# 7Segment_Hex_Display.net
KiCad netlist of a schematic drawn in EAGLE
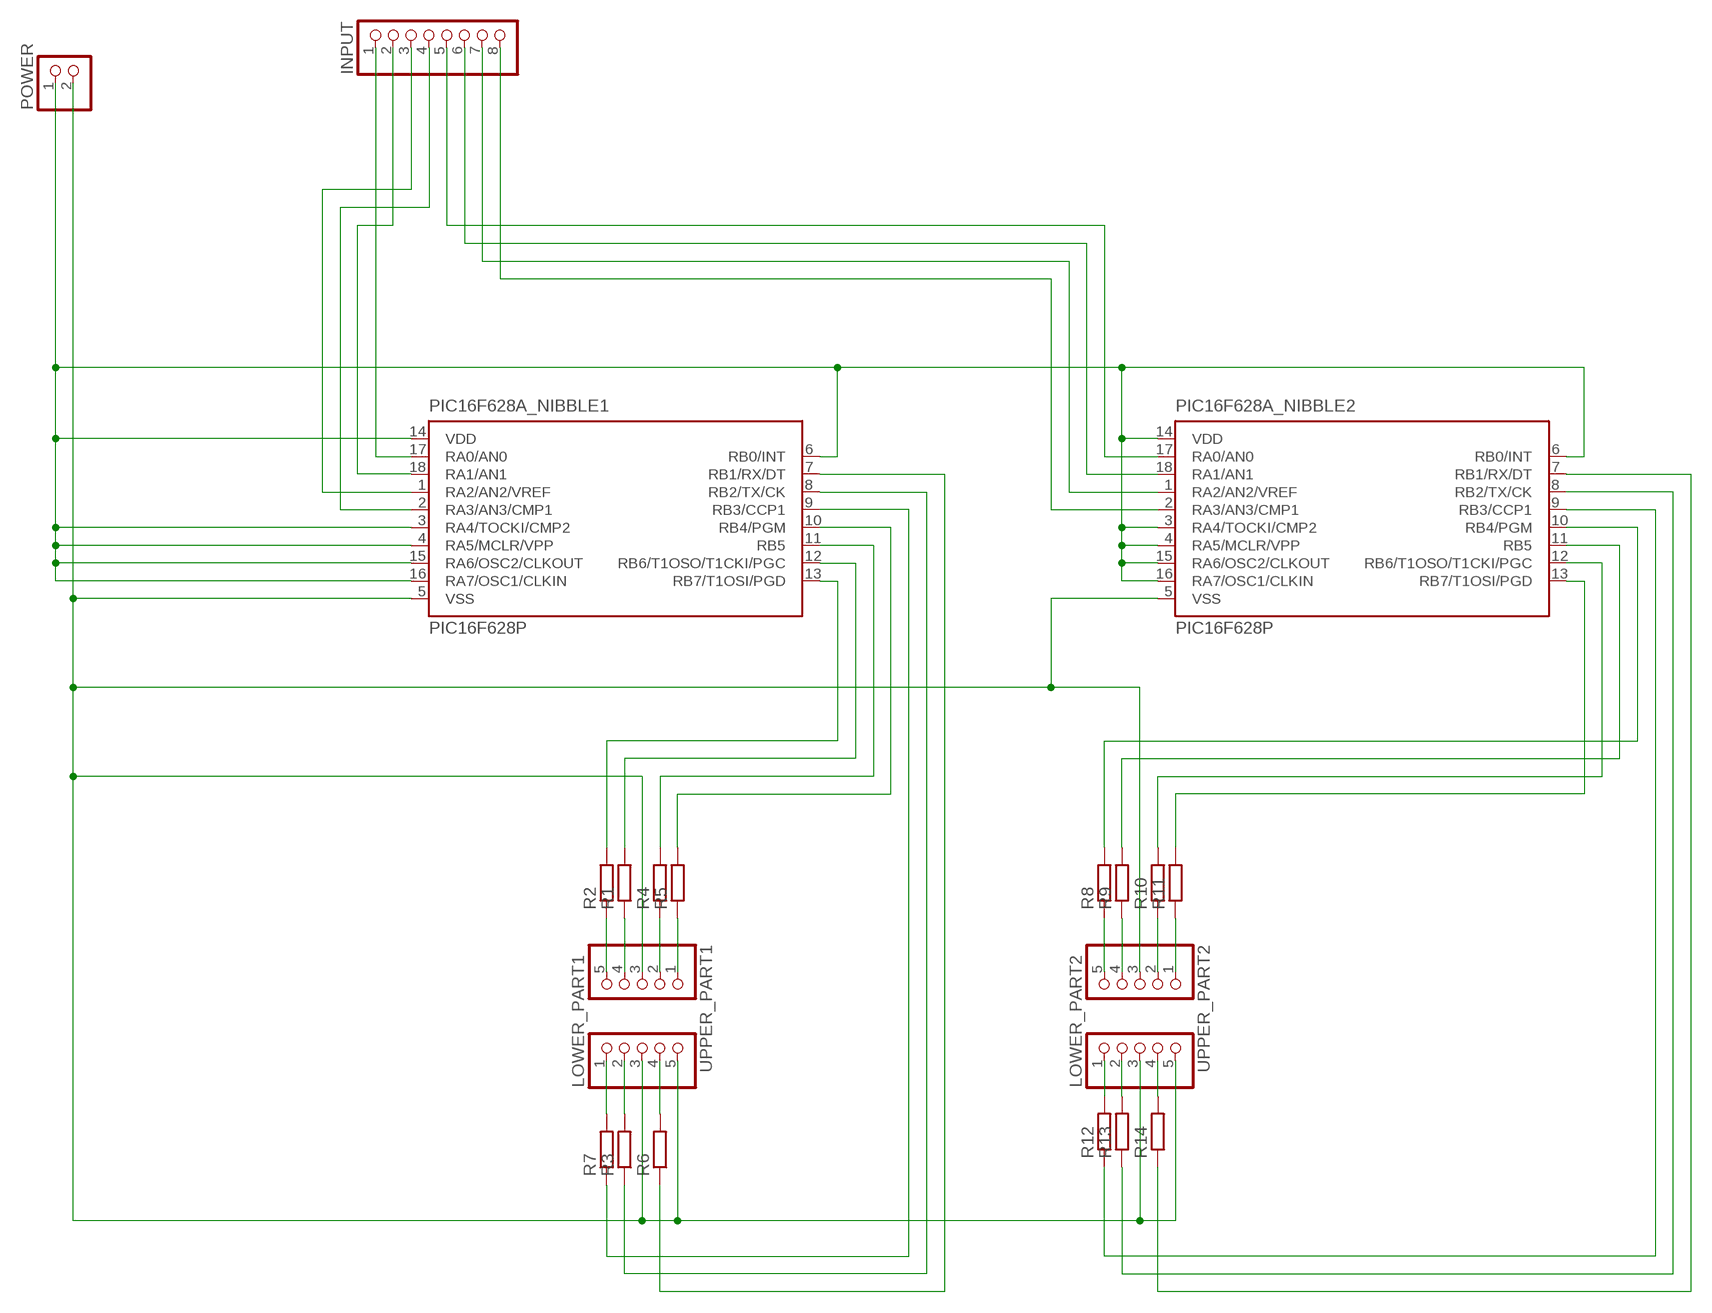
[diagram p0: schematic, sheet 1]

(export (version "E")
  (design (tool "Eeschema 10.0.6"))
  (components
    (comp (ref "INPUT")
      (value "PINHD-1X8")
      (footprint "eagle-import:1X08")
      (libsource (lib "eagle-import") (part "PINHD-1X8"))
    )
    (comp (ref "LOWER_PART1")
      (value "PINHD-1X5")
      (footprint "eagle-import:1X05")
      (libsource (lib "eagle-import") (part "PINHD-1X5"))
    )
    (comp (ref "LOWER_PART2")
      (value "PINHD-1X5")
      (footprint "eagle-import:1X05")
      (libsource (lib "eagle-import") (part "PINHD-1X5"))
    )
    (comp (ref "PIC16F628A_NIBBLE1")
      (value "PIC16F628P")
      (footprint "eagle-import:DIL18")
      (fields (field (name "MF") "MICROCHIP") (field (name "MPN") "PIC16F628-04I/P"))
      (libsource (lib "eagle-import") (part "PIC16F62P8"))
    )
    (comp (ref "PIC16F628A_NIBBLE2")
      (value "PIC16F628P")
      (footprint "eagle-import:DIL18")
      (fields (field (name "MF") "MICROCHIP") (field (name "MPN") "PIC16F628-04I/P"))
      (libsource (lib "eagle-import") (part "PIC16F62P8"))
    )
    (comp (ref "POWER")
      (value "PINHD-1X2")
      (footprint "eagle-import:1X02")
      (libsource (lib "eagle-import") (part "PINHD-1X2"))
    )
    (comp (ref "R1")
      (value "R-EU_0207/10")
      (footprint "eagle-import:0207_10")
      (libsource (lib "eagle-import") (part "R-EU_0207/10"))
    )
    (comp (ref "R2")
      (value "R-EU_0207/10")
      (footprint "eagle-import:0207_10")
      (libsource (lib "eagle-import") (part "R-EU_0207/10"))
    )
    (comp (ref "R3")
      (value "R-EU_0207/10")
      (footprint "eagle-import:0207_10")
      (libsource (lib "eagle-import") (part "R-EU_0207/10"))
    )
    (comp (ref "R4")
      (value "R-EU_0207/10")
      (footprint "eagle-import:0207_10")
      (libsource (lib "eagle-import") (part "R-EU_0207/10"))
    )
    (comp (ref "R5")
      (value "R-EU_0207/10")
      (footprint "eagle-import:0207_10")
      (libsource (lib "eagle-import") (part "R-EU_0207/10"))
    )
    (comp (ref "R6")
      (value "R-EU_0207/10")
      (footprint "eagle-import:0207_10")
      (libsource (lib "eagle-import") (part "R-EU_0207/10"))
    )
    (comp (ref "R7")
      (value "R-EU_0207/10")
      (footprint "eagle-import:0207_10")
      (libsource (lib "eagle-import") (part "R-EU_0207/10"))
    )
    (comp (ref "R8")
      (value "R-EU_0207/10")
      (footprint "eagle-import:0207_10")
      (libsource (lib "eagle-import") (part "R-EU_0207/10"))
    )
    (comp (ref "R9")
      (value "R-EU_0207/10")
      (footprint "eagle-import:0207_10")
      (libsource (lib "eagle-import") (part "R-EU_0207/10"))
    )
    (comp (ref "R10")
      (value "R-EU_0207/10")
      (footprint "eagle-import:0207_10")
      (libsource (lib "eagle-import") (part "R-EU_0207/10"))
    )
    (comp (ref "R11")
      (value "R-EU_0207/10")
      (footprint "eagle-import:0207_10")
      (libsource (lib "eagle-import") (part "R-EU_0207/10"))
    )
    (comp (ref "R12")
      (value "R-EU_0207/10")
      (footprint "eagle-import:0207_10")
      (libsource (lib "eagle-import") (part "R-EU_0207/10"))
    )
    (comp (ref "R13")
      (value "R-EU_0207/10")
      (footprint "eagle-import:0207_10")
      (libsource (lib "eagle-import") (part "R-EU_0207/10"))
    )
    (comp (ref "R14")
      (value "R-EU_0207/10")
      (footprint "eagle-import:0207_10")
      (libsource (lib "eagle-import") (part "R-EU_0207/10"))
    )
    (comp (ref "UPPER_PART1")
      (value "PINHD-1X5")
      (footprint "eagle-import:1X05")
      (libsource (lib "eagle-import") (part "PINHD-1X5"))
    )
    (comp (ref "UPPER_PART2")
      (value "PINHD-1X5")
      (footprint "eagle-import:1X05")
      (libsource (lib "eagle-import") (part "PINHD-1X5"))
    )
  )
  (nets
    (net (code "1") (name "Net-(LOWER_PART1-Pad1)") (class "Default")
      (node (ref "LOWER_PART1") (pin "1") (pinfunction "1_1") (pintype "passive"))
      (node (ref "R7") (pin "2") (pinfunction "2_2") (pintype "passive"))
    )
    (net (code "2") (name "Net-(LOWER_PART1-Pad2)") (class "Default")
      (node (ref "LOWER_PART1") (pin "2") (pinfunction "2_2") (pintype "passive"))
      (node (ref "R3") (pin "2") (pinfunction "2_2") (pintype "passive"))
    )
    (net (code "3") (name "Net-(LOWER_PART1-Pad4)") (class "Default")
      (node (ref "LOWER_PART1") (pin "4") (pinfunction "4_4") (pintype "passive"))
      (node (ref "R6") (pin "2") (pinfunction "2_2") (pintype "passive"))
    )
    (net (code "4") (name "Net-(LOWER_PART2-Pad1)") (class "Default")
      (node (ref "LOWER_PART2") (pin "1") (pinfunction "1_1") (pintype "passive"))
      (node (ref "R12") (pin "2") (pinfunction "2_2") (pintype "passive"))
    )
    (net (code "5") (name "Net-(LOWER_PART2-Pad2)") (class "Default")
      (node (ref "LOWER_PART2") (pin "2") (pinfunction "2_2") (pintype "passive"))
      (node (ref "R13") (pin "2") (pinfunction "2_2") (pintype "passive"))
    )
    (net (code "6") (name "Net-(LOWER_PART2-Pad4)") (class "Default")
      (node (ref "LOWER_PART2") (pin "4") (pinfunction "4_4") (pintype "passive"))
      (node (ref "R14") (pin "2") (pinfunction "2_2") (pintype "passive"))
    )
    (net (code "7") (name "Net-(PIC16F628A_NIBBLE1-RA0{slash}AN0)") (class "Default")
      (node (ref "INPUT") (pin "1") (pinfunction "1_1") (pintype "passive"))
      (node (ref "PIC16F628A_NIBBLE1") (pin "17") (pinfunction "RA0/AN0_17") (pintype "bidirectional"))
    )
    (net (code "8") (name "Net-(PIC16F628A_NIBBLE1-RA1{slash}AN1)") (class "Default")
      (node (ref "INPUT") (pin "2") (pinfunction "2_2") (pintype "passive"))
      (node (ref "PIC16F628A_NIBBLE1") (pin "18") (pinfunction "RA1/AN1_18") (pintype "bidirectional"))
    )
    (net (code "9") (name "Net-(PIC16F628A_NIBBLE1-RA2{slash}AN2{slash}VREF)") (class "Default")
      (node (ref "INPUT") (pin "3") (pinfunction "3_3") (pintype "passive"))
      (node (ref "PIC16F628A_NIBBLE1") (pin "1") (pinfunction "RA2/AN2/VREF_1") (pintype "bidirectional"))
    )
    (net (code "10") (name "Net-(PIC16F628A_NIBBLE1-RA3{slash}AN3{slash}CMP1)") (class "Default")
      (node (ref "INPUT") (pin "4") (pinfunction "4_4") (pintype "passive"))
      (node (ref "PIC16F628A_NIBBLE1") (pin "2") (pinfunction "RA3/AN3/CMP1_2") (pintype "bidirectional"))
    )
    (net (code "11") (name "Net-(PIC16F628A_NIBBLE1-RA4{slash}TOCKI{slash}CMP2)") (class "Default")
      (node (ref "PIC16F628A_NIBBLE1") (pin "14") (pinfunction "VDD_14") (pintype "power_in"))
      (node (ref "PIC16F628A_NIBBLE1") (pin "15") (pinfunction "RA6/OSC2/CLKOUT_15") (pintype "bidirectional"))
      (node (ref "PIC16F628A_NIBBLE1") (pin "16") (pinfunction "RA7/OSC1/CLKIN_16") (pintype "bidirectional"))
      (node (ref "PIC16F628A_NIBBLE1") (pin "3") (pinfunction "RA4/TOCKI/CMP2_3") (pintype "bidirectional"))
      (node (ref "PIC16F628A_NIBBLE1") (pin "4") (pinfunction "RA5/MCLR/VPP_4") (pintype "bidirectional"))
      (node (ref "PIC16F628A_NIBBLE1") (pin "6") (pinfunction "RB0/INT_6") (pintype "bidirectional"))
      (node (ref "PIC16F628A_NIBBLE2") (pin "14") (pinfunction "VDD_14") (pintype "power_in"))
      (node (ref "PIC16F628A_NIBBLE2") (pin "15") (pinfunction "RA6/OSC2/CLKOUT_15") (pintype "bidirectional"))
      (node (ref "PIC16F628A_NIBBLE2") (pin "16") (pinfunction "RA7/OSC1/CLKIN_16") (pintype "bidirectional"))
      (node (ref "PIC16F628A_NIBBLE2") (pin "3") (pinfunction "RA4/TOCKI/CMP2_3") (pintype "bidirectional"))
      (node (ref "PIC16F628A_NIBBLE2") (pin "4") (pinfunction "RA5/MCLR/VPP_4") (pintype "bidirectional"))
      (node (ref "PIC16F628A_NIBBLE2") (pin "6") (pinfunction "RB0/INT_6") (pintype "bidirectional"))
      (node (ref "POWER") (pin "1") (pinfunction "1_1") (pintype "passive"))
    )
    (net (code "12") (name "Net-(PIC16F628A_NIBBLE1-RB1{slash}RX{slash}DT)") (class "Default")
      (node (ref "PIC16F628A_NIBBLE1") (pin "7") (pinfunction "RB1/RX/DT_7") (pintype "bidirectional"))
      (node (ref "R6") (pin "1") (pinfunction "1_1") (pintype "passive"))
    )
    (net (code "13") (name "Net-(PIC16F628A_NIBBLE1-RB2{slash}TX{slash}CK)") (class "Default")
      (node (ref "PIC16F628A_NIBBLE1") (pin "8") (pinfunction "RB2/TX/CK_8") (pintype "bidirectional"))
      (node (ref "R3") (pin "1") (pinfunction "1_1") (pintype "passive"))
    )
    (net (code "14") (name "Net-(PIC16F628A_NIBBLE1-RB3{slash}CCP1)") (class "Default")
      (node (ref "PIC16F628A_NIBBLE1") (pin "9") (pinfunction "RB3/CCP1_9") (pintype "bidirectional"))
      (node (ref "R7") (pin "1") (pinfunction "1_1") (pintype "passive"))
    )
    (net (code "15") (name "Net-(PIC16F628A_NIBBLE1-RB4{slash}PGM)") (class "Default")
      (node (ref "PIC16F628A_NIBBLE1") (pin "10") (pinfunction "RB4/PGM_10") (pintype "bidirectional"))
      (node (ref "R5") (pin "2") (pinfunction "2_2") (pintype "passive"))
    )
    (net (code "16") (name "Net-(PIC16F628A_NIBBLE1-RB5)") (class "Default")
      (node (ref "PIC16F628A_NIBBLE1") (pin "11") (pinfunction "RB5_11") (pintype "bidirectional"))
      (node (ref "R4") (pin "2") (pinfunction "2_2") (pintype "passive"))
    )
    (net (code "17") (name "Net-(PIC16F628A_NIBBLE1-RB6{slash}T1OSO{slash}T1CKI{slash}PGC)") (class "Default")
      (node (ref "PIC16F628A_NIBBLE1") (pin "12") (pinfunction "RB6/T1OSO/T1CKI/PGC_12") (pintype "bidirectional"))
      (node (ref "R1") (pin "2") (pinfunction "2_2") (pintype "passive"))
    )
    (net (code "18") (name "Net-(PIC16F628A_NIBBLE1-RB7{slash}T1OSI{slash}PGD)") (class "Default")
      (node (ref "PIC16F628A_NIBBLE1") (pin "13") (pinfunction "RB7/T1OSI/PGD_13") (pintype "bidirectional"))
      (node (ref "R2") (pin "2") (pinfunction "2_2") (pintype "passive"))
    )
    (net (code "19") (name "Net-(PIC16F628A_NIBBLE1-VSS)") (class "Default")
      (node (ref "LOWER_PART1") (pin "3") (pinfunction "3_3") (pintype "passive"))
      (node (ref "LOWER_PART1") (pin "5") (pinfunction "5_5") (pintype "passive"))
      (node (ref "LOWER_PART2") (pin "3") (pinfunction "3_3") (pintype "passive"))
      (node (ref "LOWER_PART2") (pin "5") (pinfunction "5_5") (pintype "passive"))
      (node (ref "PIC16F628A_NIBBLE1") (pin "5") (pinfunction "VSS_5") (pintype "power_in"))
      (node (ref "PIC16F628A_NIBBLE2") (pin "5") (pinfunction "VSS_5") (pintype "power_in"))
      (node (ref "POWER") (pin "2") (pinfunction "2_2") (pintype "passive"))
      (node (ref "UPPER_PART1") (pin "3") (pinfunction "3_3") (pintype "passive"))
      (node (ref "UPPER_PART2") (pin "3") (pinfunction "3_3") (pintype "passive"))
    )
    (net (code "20") (name "Net-(PIC16F628A_NIBBLE2-RA0{slash}AN0)") (class "Default")
      (node (ref "INPUT") (pin "5") (pinfunction "5_5") (pintype "passive"))
      (node (ref "PIC16F628A_NIBBLE2") (pin "17") (pinfunction "RA0/AN0_17") (pintype "bidirectional"))
    )
    (net (code "21") (name "Net-(PIC16F628A_NIBBLE2-RA1{slash}AN1)") (class "Default")
      (node (ref "INPUT") (pin "6") (pinfunction "6_6") (pintype "passive"))
      (node (ref "PIC16F628A_NIBBLE2") (pin "18") (pinfunction "RA1/AN1_18") (pintype "bidirectional"))
    )
    (net (code "22") (name "Net-(PIC16F628A_NIBBLE2-RA2{slash}AN2{slash}VREF)") (class "Default")
      (node (ref "INPUT") (pin "7") (pinfunction "7_7") (pintype "passive"))
      (node (ref "PIC16F628A_NIBBLE2") (pin "1") (pinfunction "RA2/AN2/VREF_1") (pintype "bidirectional"))
    )
    (net (code "23") (name "Net-(PIC16F628A_NIBBLE2-RA3{slash}AN3{slash}CMP1)") (class "Default")
      (node (ref "INPUT") (pin "8") (pinfunction "8_8") (pintype "passive"))
      (node (ref "PIC16F628A_NIBBLE2") (pin "2") (pinfunction "RA3/AN3/CMP1_2") (pintype "bidirectional"))
    )
    (net (code "24") (name "Net-(PIC16F628A_NIBBLE2-RB1{slash}RX{slash}DT)") (class "Default")
      (node (ref "PIC16F628A_NIBBLE2") (pin "7") (pinfunction "RB1/RX/DT_7") (pintype "bidirectional"))
      (node (ref "R14") (pin "1") (pinfunction "1_1") (pintype "passive"))
    )
    (net (code "25") (name "Net-(PIC16F628A_NIBBLE2-RB2{slash}TX{slash}CK)") (class "Default")
      (node (ref "PIC16F628A_NIBBLE2") (pin "8") (pinfunction "RB2/TX/CK_8") (pintype "bidirectional"))
      (node (ref "R13") (pin "1") (pinfunction "1_1") (pintype "passive"))
    )
    (net (code "26") (name "Net-(PIC16F628A_NIBBLE2-RB3{slash}CCP1)") (class "Default")
      (node (ref "PIC16F628A_NIBBLE2") (pin "9") (pinfunction "RB3/CCP1_9") (pintype "bidirectional"))
      (node (ref "R12") (pin "1") (pinfunction "1_1") (pintype "passive"))
    )
    (net (code "27") (name "Net-(PIC16F628A_NIBBLE2-RB4{slash}PGM)") (class "Default")
      (node (ref "PIC16F628A_NIBBLE2") (pin "10") (pinfunction "RB4/PGM_10") (pintype "bidirectional"))
      (node (ref "R8") (pin "2") (pinfunction "2_2") (pintype "passive"))
    )
    (net (code "28") (name "Net-(PIC16F628A_NIBBLE2-RB5)") (class "Default")
      (node (ref "PIC16F628A_NIBBLE2") (pin "11") (pinfunction "RB5_11") (pintype "bidirectional"))
      (node (ref "R9") (pin "2") (pinfunction "2_2") (pintype "passive"))
    )
    (net (code "29") (name "Net-(PIC16F628A_NIBBLE2-RB6{slash}T1OSO{slash}T1CKI{slash}PGC)") (class "Default")
      (node (ref "PIC16F628A_NIBBLE2") (pin "12") (pinfunction "RB6/T1OSO/T1CKI/PGC_12") (pintype "bidirectional"))
      (node (ref "R10") (pin "2") (pinfunction "2_2") (pintype "passive"))
    )
    (net (code "30") (name "Net-(PIC16F628A_NIBBLE2-RB7{slash}T1OSI{slash}PGD)") (class "Default")
      (node (ref "PIC16F628A_NIBBLE2") (pin "13") (pinfunction "RB7/T1OSI/PGD_13") (pintype "bidirectional"))
      (node (ref "R11") (pin "2") (pinfunction "2_2") (pintype "passive"))
    )
    (net (code "31") (name "Net-(R1-Pad1)") (class "Default")
      (node (ref "R1") (pin "1") (pinfunction "1_1") (pintype "passive"))
      (node (ref "UPPER_PART1") (pin "4") (pinfunction "4_4") (pintype "passive"))
    )
    (net (code "32") (name "Net-(R2-Pad1)") (class "Default")
      (node (ref "R2") (pin "1") (pinfunction "1_1") (pintype "passive"))
      (node (ref "UPPER_PART1") (pin "5") (pinfunction "5_5") (pintype "passive"))
    )
    (net (code "33") (name "Net-(R4-Pad1)") (class "Default")
      (node (ref "R4") (pin "1") (pinfunction "1_1") (pintype "passive"))
      (node (ref "UPPER_PART1") (pin "2") (pinfunction "2_2") (pintype "passive"))
    )
    (net (code "34") (name "Net-(R5-Pad1)") (class "Default")
      (node (ref "R5") (pin "1") (pinfunction "1_1") (pintype "passive"))
      (node (ref "UPPER_PART1") (pin "1") (pinfunction "1_1") (pintype "passive"))
    )
    (net (code "35") (name "Net-(R8-Pad1)") (class "Default")
      (node (ref "R8") (pin "1") (pinfunction "1_1") (pintype "passive"))
      (node (ref "UPPER_PART2") (pin "5") (pinfunction "5_5") (pintype "passive"))
    )
    (net (code "36") (name "Net-(R9-Pad1)") (class "Default")
      (node (ref "R9") (pin "1") (pinfunction "1_1") (pintype "passive"))
      (node (ref "UPPER_PART2") (pin "4") (pinfunction "4_4") (pintype "passive"))
    )
    (net (code "37") (name "Net-(R10-Pad1)") (class "Default")
      (node (ref "R10") (pin "1") (pinfunction "1_1") (pintype "passive"))
      (node (ref "UPPER_PART2") (pin "2") (pinfunction "2_2") (pintype "passive"))
    )
    (net (code "38") (name "Net-(R11-Pad1)") (class "Default")
      (node (ref "R11") (pin "1") (pinfunction "1_1") (pintype "passive"))
      (node (ref "UPPER_PART2") (pin "1") (pinfunction "1_1") (pintype "passive"))
    )
  )
)
